# senror_input.net
KiCad netlist of a schematic drawn in Altium Designer
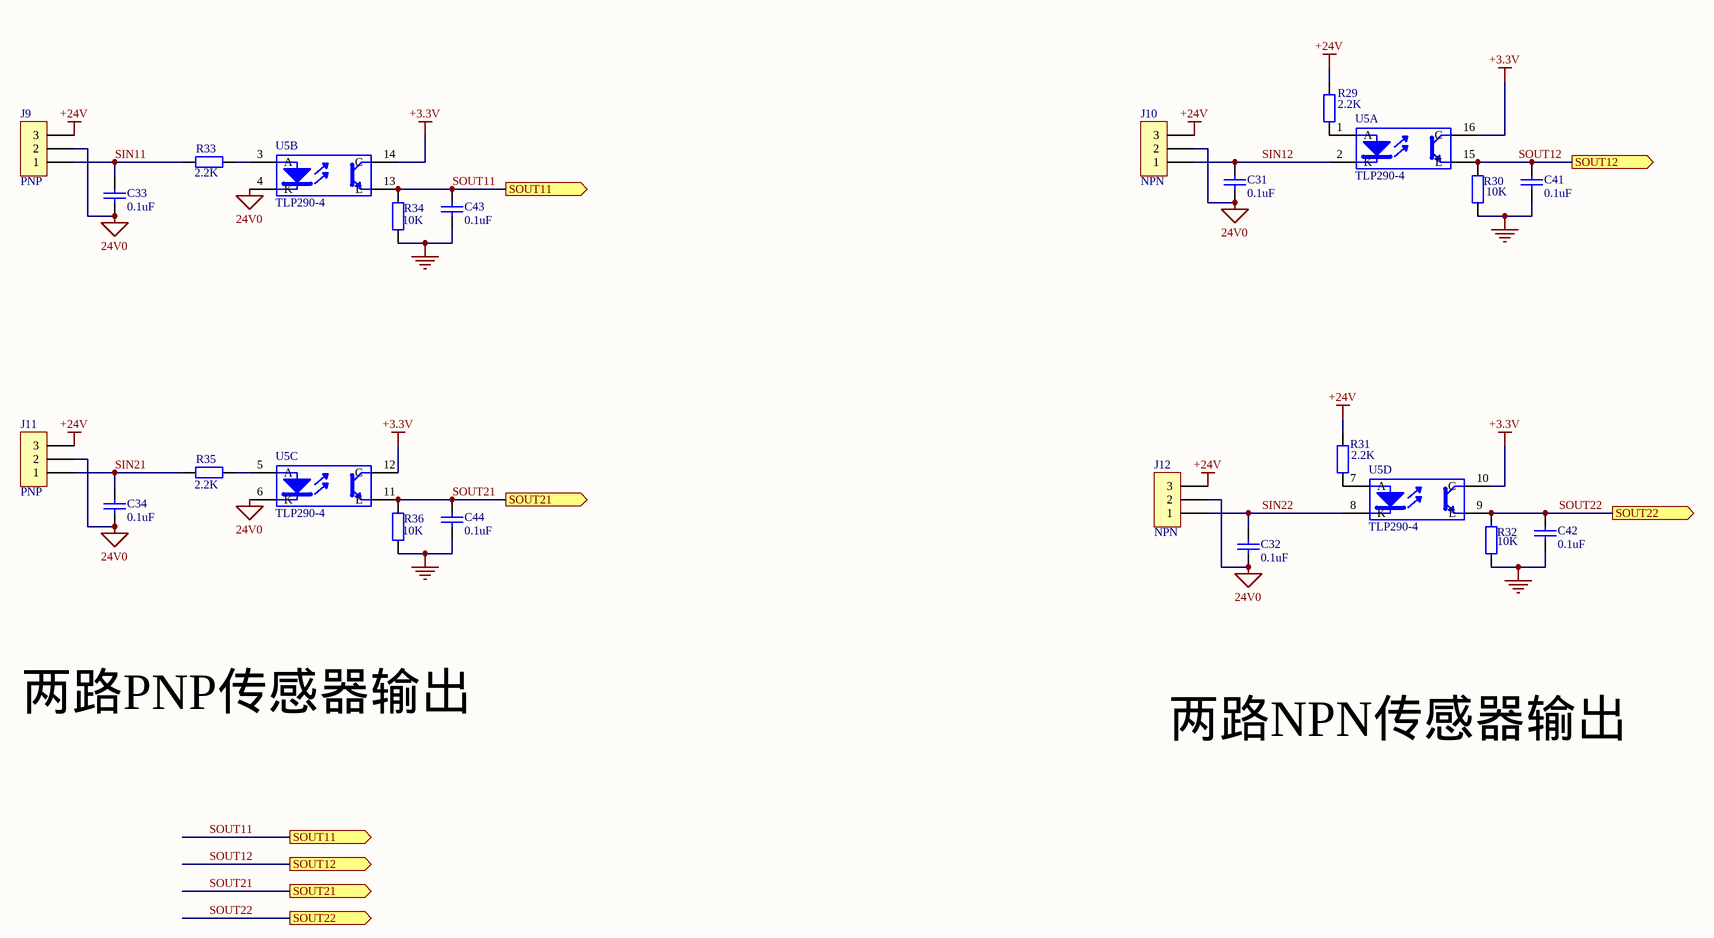
[diagram p0: senror_input.SchDoc]

(export (version "E")
  (design (tool "Eeschema 10.0.6"))
  (components
    (comp (ref "C31")
      (value "0.1uF")
      (footprint "0805_CAP")
      (description "Capacitor")
      (fields (field (name "PUBLISHER") "Altium Limited"))
      (libsource (lib "Miscellaneous Devices") (part "Cap"))
    )
    (comp (ref "C32")
      (value "0.1uF")
      (footprint "0805_CAP")
      (description "Capacitor")
      (fields (field (name "PUBLISHER") "Altium Limited"))
      (libsource (lib "Miscellaneous Devices") (part "Cap"))
    )
    (comp (ref "C33")
      (value "0.1uF")
      (footprint "0805_CAP")
      (description "Capacitor")
      (fields (field (name "PUBLISHER") "Altium Limited"))
      (libsource (lib "Miscellaneous Devices") (part "Cap"))
    )
    (comp (ref "C34")
      (value "0.1uF")
      (footprint "0805_CAP")
      (description "Capacitor")
      (fields (field (name "PUBLISHER") "Altium Limited"))
      (libsource (lib "Miscellaneous Devices") (part "Cap"))
    )
    (comp (ref "C41")
      (value "0.1uF")
      (footprint "0805_CAP")
      (description "Capacitor")
      (fields (field (name "PUBLISHER") "Altium Limited"))
      (libsource (lib "Miscellaneous Devices") (part "Cap"))
    )
    (comp (ref "C42")
      (value "0.1uF")
      (footprint "0805_CAP")
      (description "Capacitor")
      (fields (field (name "PUBLISHER") "Altium Limited"))
      (libsource (lib "Miscellaneous Devices") (part "Cap"))
    )
    (comp (ref "C43")
      (value "0.1uF")
      (footprint "0805_CAP")
      (description "Capacitor")
      (fields (field (name "PUBLISHER") "Altium Limited"))
      (libsource (lib "Miscellaneous Devices") (part "Cap"))
    )
    (comp (ref "C44")
      (value "0.1uF")
      (footprint "0805_CAP")
      (description "Capacitor")
      (fields (field (name "PUBLISHER") "Altium Limited"))
      (libsource (lib "Miscellaneous Devices") (part "Cap"))
    )
    (comp (ref "J9")
      (value "HEADER1X3")
      (footprint "VH3.96_3P")
      (fields (field (name "ALTIUM_UNNAMED_1") "PNP"))
      (libsource (lib "myIntegrated_Library1") (part "HEADER1X3"))
    )
    (comp (ref "J10")
      (value "HEADER1X3")
      (footprint "VH3.96_3P")
      (fields (field (name "ALTIUM_UNNAMED_1") "NPN"))
      (libsource (lib "myIntegrated_Library1") (part "HEADER1X3"))
    )
    (comp (ref "J11")
      (value "HEADER1X3")
      (footprint "VH3.96_3P")
      (fields (field (name "ALTIUM_UNNAMED_1") "PNP"))
      (libsource (lib "myIntegrated_Library1") (part "HEADER1X3"))
    )
    (comp (ref "J12")
      (value "HEADER1X3")
      (footprint "VH3.96_3P")
      (fields (field (name "ALTIUM_UNNAMED_1") "NPN"))
      (libsource (lib "myIntegrated_Library1") (part "HEADER1X3"))
    )
    (comp (ref "R29")
      (value "2.2K")
      (footprint "0805_RES")
      (description "Resistor")
      (fields (field (name "PUBLISHER") "Altium Limited"))
      (libsource (lib "") (part "Res2_1"))
    )
    (comp (ref "R30")
      (value "10K")
      (footprint "0805_RES")
      (description "Resistor")
      (fields (field (name "PUBLISHER") "Altium Limited"))
      (libsource (lib "") (part "Res2_1"))
    )
    (comp (ref "R31")
      (value "2.2K")
      (footprint "0805_RES")
      (description "Resistor")
      (fields (field (name "PUBLISHER") "Altium Limited"))
      (libsource (lib "") (part "Res2_1"))
    )
    (comp (ref "R32")
      (value "10K")
      (footprint "0805_RES")
      (description "Resistor")
      (fields (field (name "PUBLISHER") "Altium Limited"))
      (libsource (lib "") (part "Res2_1"))
    )
    (comp (ref "R33")
      (value "2.2K")
      (footprint "0805_RES")
      (description "Resistor")
      (fields (field (name "PUBLISHER") "Altium Limited"))
      (libsource (lib "Miscellaneous Devices") (part "Res2"))
    )
    (comp (ref "R34")
      (value "10K")
      (footprint "0805_RES")
      (description "Resistor")
      (fields (field (name "PUBLISHER") "Altium Limited"))
      (libsource (lib "") (part "Res2_1"))
    )
    (comp (ref "R35")
      (value "2.2K")
      (footprint "0805_RES")
      (description "Resistor")
      (fields (field (name "PUBLISHER") "Altium Limited"))
      (libsource (lib "Miscellaneous Devices") (part "Res2"))
    )
    (comp (ref "R36")
      (value "10K")
      (footprint "0805_RES")
      (description "Resistor")
      (fields (field (name "PUBLISHER") "Altium Limited"))
      (libsource (lib "") (part "Res2_1"))
    )
    (comp (ref "U5") (value "TLP290-4") (footprint "SO16") (libsource (lib "WH V20") (part "TLP521-4")))
  )
  (nets
    (net (code "1") (name "+3.3V") (class "Default")
      (node (ref "U5") (pin "10") (pinfunction "C_10") (pintype "passive"))
      (node (ref "U5") (pin "12") (pinfunction "C_12") (pintype "passive"))
      (node (ref "U5") (pin "14") (pinfunction "C_14") (pintype "passive"))
      (node (ref "U5") (pin "16") (pinfunction "C_16") (pintype "passive"))
    )
    (net (code "2") (name "+24V") (class "Default")
      (node (ref "J10") (pin "3") (pinfunction "3_3") (pintype "passive"))
      (node (ref "J11") (pin "3") (pinfunction "3_3") (pintype "passive"))
      (node (ref "J12") (pin "3") (pinfunction "3_3") (pintype "passive"))
      (node (ref "J9") (pin "3") (pinfunction "3_3") (pintype "passive"))
      (node (ref "R29") (pin "1") (pinfunction "1_1") (pintype "passive"))
      (node (ref "R31") (pin "1") (pinfunction "1_1") (pintype "passive"))
    )
    (net (code "3") (name "/SIN11") (class "Default")
      (node (ref "C33") (pin "1") (pinfunction "1_1") (pintype "passive"))
      (node (ref "J9") (pin "1") (pinfunction "1_1") (pintype "passive"))
      (node (ref "R33") (pin "1") (pinfunction "1_1") (pintype "passive"))
    )
    (net (code "4") (name "/SIN12") (class "Default")
      (node (ref "C31") (pin "1") (pinfunction "1_1") (pintype "passive"))
      (node (ref "J10") (pin "1") (pinfunction "1_1") (pintype "passive"))
      (node (ref "U5") (pin "2") (pinfunction "K_2") (pintype "passive"))
    )
    (net (code "5") (name "/SIN21") (class "Default")
      (node (ref "C34") (pin "1") (pinfunction "1_1") (pintype "passive"))
      (node (ref "J11") (pin "1") (pinfunction "1_1") (pintype "passive"))
      (node (ref "R35") (pin "1") (pinfunction "1_1") (pintype "passive"))
    )
    (net (code "6") (name "/SIN22") (class "Default")
      (node (ref "C32") (pin "1") (pinfunction "1_1") (pintype "passive"))
      (node (ref "J12") (pin "1") (pinfunction "1_1") (pintype "passive"))
      (node (ref "U5") (pin "8") (pinfunction "K_8") (pintype "passive"))
    )
    (net (code "7") (name "/SOUT11") (class "Default")
      (node (ref "C43") (pin "1") (pinfunction "1_1") (pintype "passive"))
      (node (ref "R34") (pin "1") (pinfunction "1_1") (pintype "passive"))
      (node (ref "U5") (pin "13") (pinfunction "E_13") (pintype "passive"))
    )
    (net (code "8") (name "/SOUT12") (class "Default")
      (node (ref "C41") (pin "1") (pinfunction "1_1") (pintype "passive"))
      (node (ref "R30") (pin "1") (pinfunction "1_1") (pintype "passive"))
      (node (ref "U5") (pin "15") (pinfunction "E_15") (pintype "passive"))
    )
    (net (code "9") (name "/SOUT21") (class "Default")
      (node (ref "C44") (pin "1") (pinfunction "1_1") (pintype "passive"))
      (node (ref "R36") (pin "1") (pinfunction "1_1") (pintype "passive"))
      (node (ref "U5") (pin "11") (pinfunction "E_11") (pintype "passive"))
    )
    (net (code "10") (name "/SOUT22") (class "Default")
      (node (ref "C42") (pin "1") (pinfunction "1_1") (pintype "passive"))
      (node (ref "R32") (pin "1") (pinfunction "1_1") (pintype "passive"))
      (node (ref "U5") (pin "9") (pinfunction "E_9") (pintype "passive"))
    )
    (net (code "11") (name "24V0") (class "Default")
      (node (ref "C31") (pin "2") (pinfunction "2_2") (pintype "passive"))
      (node (ref "C32") (pin "2") (pinfunction "2_2") (pintype "passive"))
      (node (ref "C33") (pin "2") (pinfunction "2_2") (pintype "passive"))
      (node (ref "C34") (pin "2") (pinfunction "2_2") (pintype "passive"))
      (node (ref "J10") (pin "2") (pinfunction "2_2") (pintype "passive"))
      (node (ref "J11") (pin "2") (pinfunction "2_2") (pintype "passive"))
      (node (ref "J12") (pin "2") (pinfunction "2_2") (pintype "passive"))
      (node (ref "J9") (pin "2") (pinfunction "2_2") (pintype "passive"))
      (node (ref "U5") (pin "4") (pinfunction "K_4") (pintype "passive"))
      (node (ref "U5") (pin "6") (pinfunction "K_6") (pintype "passive"))
    )
    (net (code "12") (name "GND") (class "Default")
      (node (ref "C41") (pin "2") (pinfunction "2_2") (pintype "passive"))
      (node (ref "C42") (pin "2") (pinfunction "2_2") (pintype "passive"))
      (node (ref "C43") (pin "2") (pinfunction "2_2") (pintype "passive"))
      (node (ref "C44") (pin "2") (pinfunction "2_2") (pintype "passive"))
      (node (ref "R30") (pin "2") (pinfunction "2_2") (pintype "passive"))
      (node (ref "R32") (pin "2") (pinfunction "2_2") (pintype "passive"))
      (node (ref "R34") (pin "2") (pinfunction "2_2") (pintype "passive"))
      (node (ref "R36") (pin "2") (pinfunction "2_2") (pintype "passive"))
    )
    (net (code "13") (name "Net-(U5A-A)") (class "Default")
      (node (ref "R29") (pin "2") (pinfunction "2_2") (pintype "passive"))
      (node (ref "U5") (pin "1") (pinfunction "A_1") (pintype "passive"))
    )
    (net (code "14") (name "Net-(U5B-A)") (class "Default")
      (node (ref "R33") (pin "2") (pinfunction "2_2") (pintype "passive"))
      (node (ref "U5") (pin "3") (pinfunction "A_3") (pintype "passive"))
    )
    (net (code "15") (name "Net-(U5C-A)") (class "Default")
      (node (ref "R35") (pin "2") (pinfunction "2_2") (pintype "passive"))
      (node (ref "U5") (pin "5") (pinfunction "A_5") (pintype "passive"))
    )
    (net (code "16") (name "Net-(U5D-A)") (class "Default")
      (node (ref "R31") (pin "2") (pinfunction "2_2") (pintype "passive"))
      (node (ref "U5") (pin "7") (pinfunction "A_7") (pintype "passive"))
    )
  )
)
